# Hi_Impedance_Voltage_Divider_v1_1.net
KiCad netlist of a schematic drawn in EAGLE
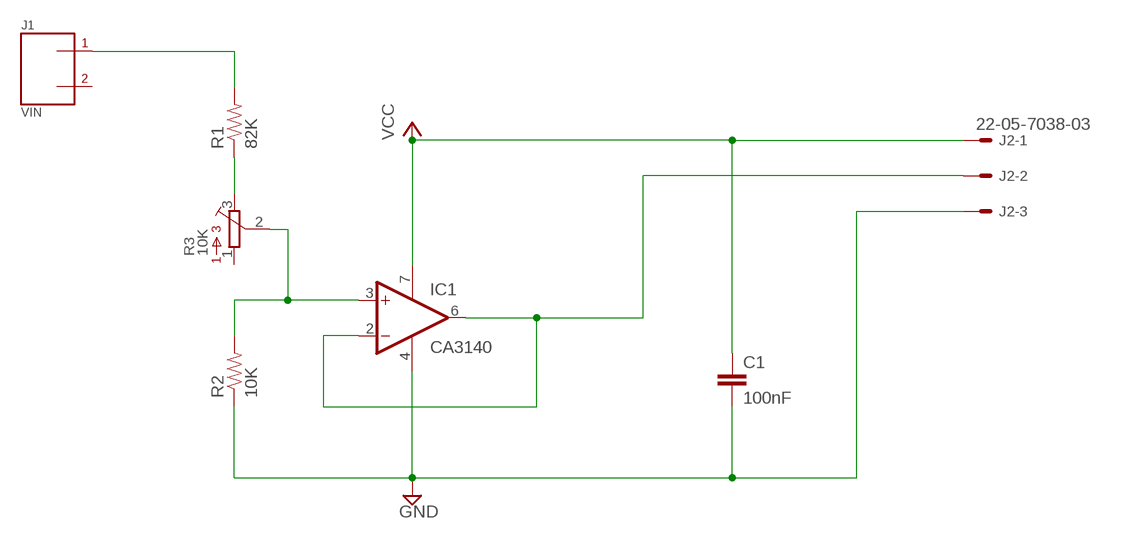
[diagram p0: schematic, sheet 1]

(export (version "E")
  (design (tool "Eeschema 10.0.6"))
  (components
    (comp (ref "C1")
      (value "100nF")
      (footprint "eagle-import:CAP-PTH-5MM")
      (libsource (lib "eagle-import") (part "CAPPTH1"))
    )
    (comp (ref "IC1")
      (value "CA3140")
      (footprint "eagle-import:DIL08")
      (libsource (lib "eagle-import") (part "1AMP_P7+4N"))
    )
    (comp (ref "J1")
      (value "VIN")
      (footprint "eagle-import:J2-508MM")
      (libsource (lib "eagle-import") (part "J2-508MM"))
    )
    (comp (ref "J2")
      (value "22-05-7038-03")
      (footprint "eagle-import:7395-03")
      (libsource (lib "eagle-import") (part "22-?-0305-7038"))
    )
    (comp (ref "R1")
      (value "82K")
      (footprint "eagle-import:AXIAL-0.3")
      (libsource (lib "eagle-import") (part "RESISTORAXIAL-0.3"))
    )
    (comp (ref "R2")
      (value "10K")
      (footprint "eagle-import:AXIAL-0.3")
      (libsource (lib "eagle-import") (part "RESISTORAXIAL-0.3"))
    )
    (comp (ref "R3")
      (value "10K")
      (footprint "eagle-import:3386W")
      (libsource (lib "eagle-import") (part "3386-W"))
    )
  )
  (nets
    (net (code "1") (name "GND") (class "Default")
      (node (ref "C1") (pin "2") (pinfunction "2_2") (pintype "passive"))
      (node (ref "IC1") (pin "4") (pinfunction "V-_4") (pintype "power_in"))
      (node (ref "J2") (pin "3") (pinfunction "S_3") (pintype "passive"))
      (node (ref "R2") (pin "P$1") (pinfunction "1_P$1") (pintype "passive"))
    )
    (net (code "2") (name "Net-(IC1-+IN)") (class "Default")
      (node (ref "IC1") (pin "3") (pinfunction "+IN_3") (pintype "input"))
      (node (ref "R2") (pin "P$2") (pinfunction "2_P$2") (pintype "passive"))
      (node (ref "R3") (pin "2") (pinfunction "2_2") (pintype "passive"))
    )
    (net (code "3") (name "Net-(IC1--IN)") (class "Default")
      (node (ref "IC1") (pin "2") (pinfunction "-IN_2") (pintype "input"))
      (node (ref "IC1") (pin "6") (pinfunction "OUT_6") (pintype "output"))
      (node (ref "J2") (pin "2") (pinfunction "S_2") (pintype "passive"))
    )
    (net (code "4") (name "Net-(R1-1)") (class "Default")
      (node (ref "R1") (pin "P$1") (pinfunction "1_P$1") (pintype "passive"))
      (node (ref "R3") (pin "3") (pinfunction "3_3") (pintype "passive"))
    )
    (net (code "5") (name "Net-(R1-2)") (class "Default")
      (node (ref "J1") (pin "P$1") (pinfunction "P$1_P$1") (pintype "bidirectional"))
      (node (ref "R1") (pin "P$2") (pinfunction "2_P$2") (pintype "passive"))
    )
    (net (code "6") (name "VCC") (class "Default")
      (node (ref "C1") (pin "1") (pinfunction "1_1") (pintype "passive"))
      (node (ref "IC1") (pin "7") (pinfunction "V+_7") (pintype "power_in"))
      (node (ref "J2") (pin "1") (pinfunction "S_1") (pintype "passive"))
    )
    (net (code "7") (name "unconnected-(J1-PadP$2)") (class "Default")
      (node (ref "J1") (pin "P$2") (pinfunction "P$2_P$2") (pintype "bidirectional"))
    )
    (net (code "8") (name "unconnected-(R3-Pad1)") (class "Default")
      (node (ref "R3") (pin "1") (pinfunction "1_1") (pintype "passive"))
    )
  )
)
